# SERIAL_FMU3_REV_C.net
KiCad netlist of a schematic drawn in Altium Designer
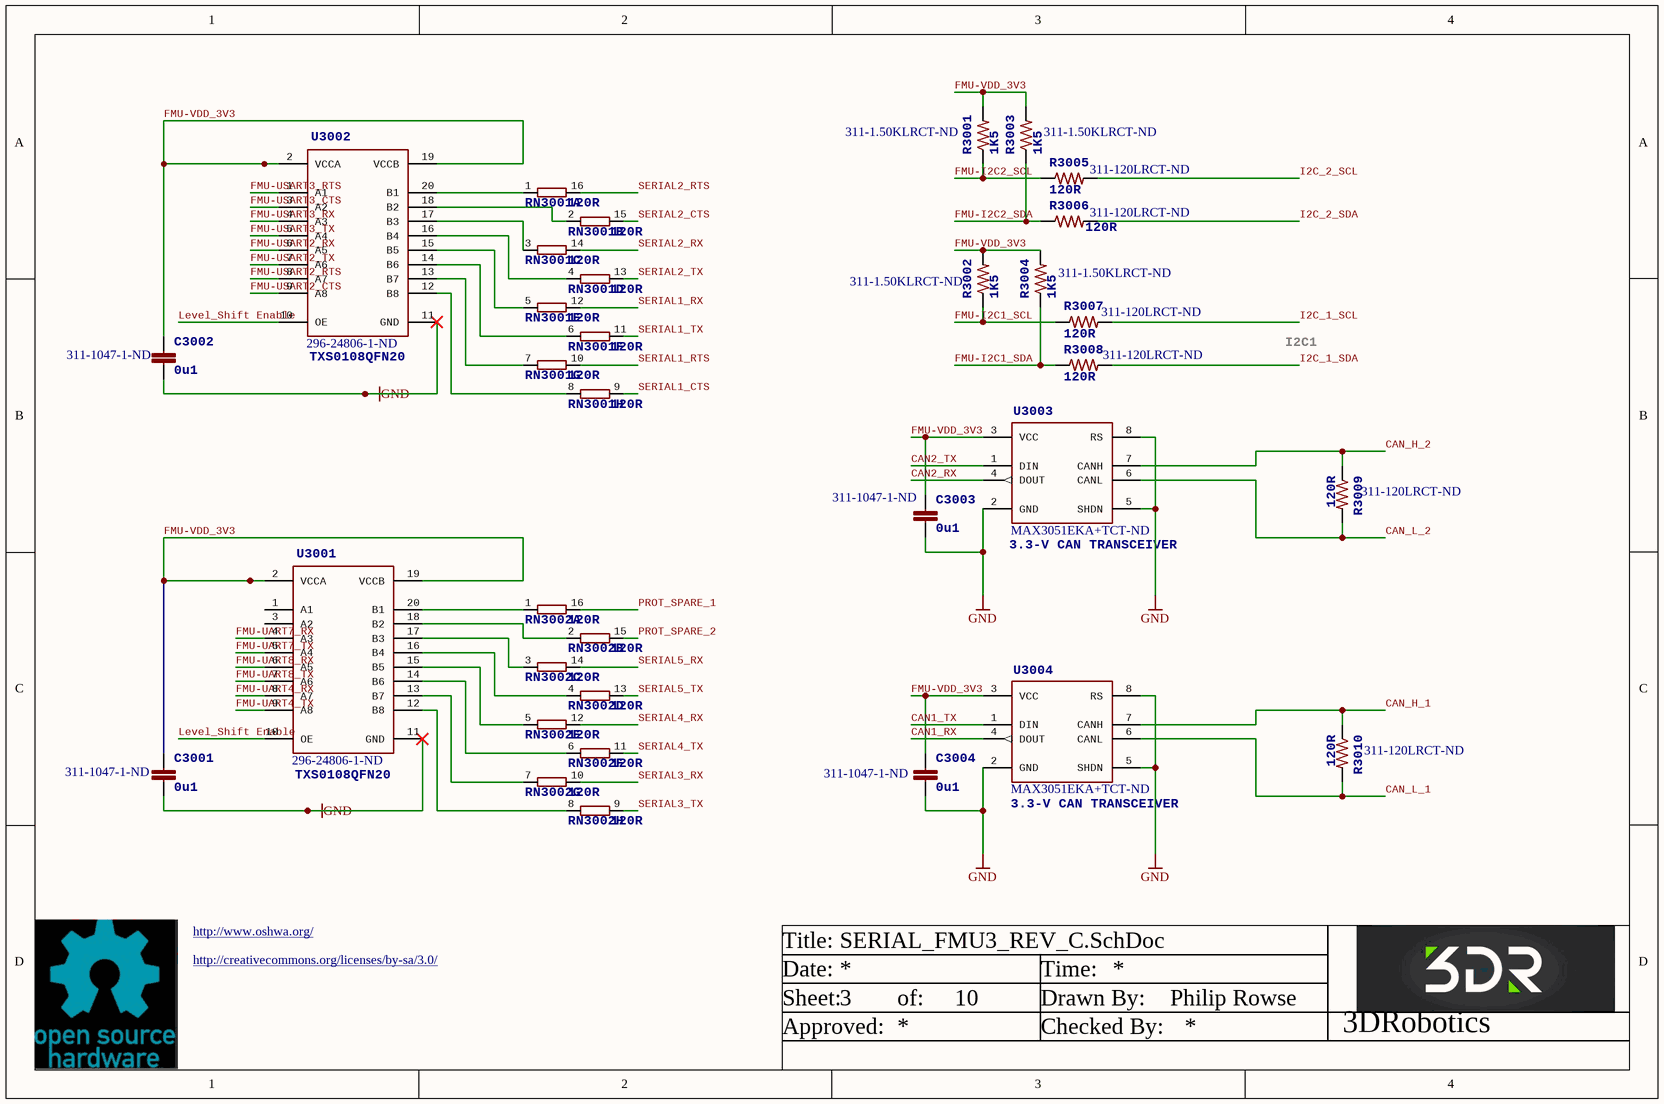
[diagram p0: SERIAL_FMU3_REV_C.SchDoc]

(export (version "E")
  (design (tool "Eeschema 10.0.6"))
  (components
    (comp (ref "C3001")
      (value "0u1")
      (footprint "0402-CAP")
      (description "CAP CER 0.1UF 16V Y5V 0402")
      (fields
        (field (name "PARTNO") "CC0402ZRY5V7BB104")
        (field (name "SUPPLIER PART NUMBER 1") "311-1047-1-ND")
        (field (name "3DR_PARTNO") "ECM0700")
      )
      (libsource (lib "pixhawk2") (part "CAP0402"))
    )
    (comp (ref "C3002")
      (value "0u1")
      (footprint "0402-CAP")
      (description "CAP CER 0.1UF 16V Y5V 0402")
      (fields
        (field (name "PARTNO") "CC0402ZRY5V7BB104")
        (field (name "SUPPLIER PART NUMBER 1") "311-1047-1-ND")
        (field (name "3DR_PARTNO") "ECM0700")
      )
      (libsource (lib "pixhawk2") (part "CAP0402"))
    )
    (comp (ref "C3003")
      (value "0u1")
      (footprint "0402-CAP")
      (description "CAP CER 0.1UF 16V Y5V 0402")
      (fields
        (field (name "PARTNO") "CC0402ZRY5V7BB104")
        (field (name "SUPPLIER PART NUMBER 1") "311-1047-1-ND")
        (field (name "3DR_PARTNO") "ECM0700")
      )
      (libsource (lib "pixhawk2") (part "CAP0402"))
    )
    (comp (ref "C3004")
      (value "0u1")
      (footprint "0402-CAP")
      (description "CAP CER 0.1UF 16V Y5V 0402")
      (fields
        (field (name "PARTNO") "CC0402ZRY5V7BB104")
        (field (name "SUPPLIER PART NUMBER 1") "311-1047-1-ND")
        (field (name "3DR_PARTNO") "ECM0700")
      )
      (libsource (lib "pixhawk2") (part "CAP0402"))
    )
    (comp (ref "R3001")
      (value "1K5")
      (footprint "0402-RES")
      (description "RES 1.5K OHM 1/16W 1% 0402 SMD")
      (fields
        (field (name "PARTNO") "RC0402FR-071K5L")
        (field (name "SUPPLIER PART NUMBER 1") "311-1.50KLRCT-ND")
        (field (name "3DR_PARTNO") "ECM0803")
      )
      (libsource (lib "pixhawk2") (part "RESISTOR0402-RES"))
    )
    (comp (ref "R3002")
      (value "1K5")
      (footprint "0402-RES")
      (description "RES 1.5K OHM 1/16W 1% 0402 SMD")
      (fields
        (field (name "PARTNO") "RC0402FR-071K5L")
        (field (name "SUPPLIER PART NUMBER 1") "311-1.50KLRCT-ND")
        (field (name "3DR_PARTNO") "ECM0803")
      )
      (libsource (lib "pixhawk2") (part "RESISTOR0402-RES"))
    )
    (comp (ref "R3003")
      (value "1K5")
      (footprint "0402-RES")
      (description "RES 1.5K OHM 1/16W 1% 0402 SMD")
      (fields
        (field (name "PARTNO") "RC0402FR-071K5L")
        (field (name "SUPPLIER PART NUMBER 1") "311-1.50KLRCT-ND")
        (field (name "3DR_PARTNO") "ECM0803")
      )
      (libsource (lib "pixhawk2") (part "RESISTOR0402-RES"))
    )
    (comp (ref "R3004")
      (value "1K5")
      (footprint "0402-RES")
      (description "RES 1.5K OHM 1/16W 1% 0402 SMD")
      (fields
        (field (name "PARTNO") "RC0402FR-071K5L")
        (field (name "SUPPLIER PART NUMBER 1") "311-1.50KLRCT-ND")
        (field (name "3DR_PARTNO") "ECM0803")
      )
      (libsource (lib "pixhawk2") (part "RESISTOR0402-RES"))
    )
    (comp (ref "R3005")
      (value "120R")
      (footprint "0402-RES")
      (description "RES 120 OHM 1/16W 1% 0402 SMD")
      (fields
        (field (name "PARTNO") "RC0402FR-07120RL")
        (field (name "SUPPLIER PART NUMBER 1") "311-120LRCT-ND")
        (field (name "3DR_PARTNO") "ECM0820")
      )
      (libsource (lib "pixhawk2") (part "RESISTOR0402-RES"))
    )
    (comp (ref "R3006")
      (value "120R")
      (footprint "0402-RES")
      (description "RES 120 OHM 1/16W 1% 0402 SMD")
      (fields
        (field (name "PARTNO") "RC0402FR-07120RL")
        (field (name "SUPPLIER PART NUMBER 1") "311-120LRCT-ND")
        (field (name "3DR_PARTNO") "ECM0820")
      )
      (libsource (lib "pixhawk2") (part "RESISTOR0402-RES"))
    )
    (comp (ref "R3007")
      (value "120R")
      (footprint "0402-RES")
      (description "RES 120 OHM 1/16W 1% 0402 SMD")
      (fields
        (field (name "PARTNO") "RC0402FR-07120RL")
        (field (name "SUPPLIER PART NUMBER 1") "311-120LRCT-ND")
        (field (name "3DR_PARTNO") "ECM0820")
      )
      (libsource (lib "pixhawk2") (part "RESISTOR0402-RES"))
    )
    (comp (ref "R3008")
      (value "120R")
      (footprint "0402-RES")
      (description "RES 120 OHM 1/16W 1% 0402 SMD")
      (fields
        (field (name "PARTNO") "RC0402FR-07120RL")
        (field (name "SUPPLIER PART NUMBER 1") "311-120LRCT-ND")
        (field (name "3DR_PARTNO") "ECM0820")
      )
      (libsource (lib "pixhawk2") (part "RESISTOR0402-RES"))
    )
    (comp (ref "R3009")
      (value "120R")
      (footprint "0402-RES")
      (description "RES 120 OHM 1/16W 1% 0402 SMD")
      (fields
        (field (name "PARTNO") "RC0402FR-07120RL")
        (field (name "SUPPLIER PART NUMBER 1") "311-120LRCT-ND")
        (field (name "3DR_PARTNO") "ECM0820")
      )
      (libsource (lib "pixhawk2") (part "RESISTOR0402-RES"))
    )
    (comp (ref "R3010")
      (value "120R")
      (footprint "0402-RES")
      (description "RES 120 OHM 1/16W 1% 0402 SMD")
      (fields
        (field (name "PARTNO") "RC0402FR-07120RL")
        (field (name "SUPPLIER PART NUMBER 1") "311-120LRCT-ND")
        (field (name "3DR_PARTNO") "ECM0820")
      )
      (libsource (lib "pixhawk2") (part "RESISTOR0402-RES"))
    )
    (comp (ref "RN3001")
      (value "120R")
      (footprint "EXB2HV")
      (description "RES ARRAY 120 OHM 8 RES 1506")
      (fields (field (name "PARTNO") "EXB-2HV121JV") (field (name "3DR_PARTNO") "EMC"))
      (libsource (lib "pixhawk2") (part "8R-NEXB2HV-120R"))
    )
    (comp (ref "RN3002")
      (value "120R")
      (footprint "EXB2HV")
      (description "RES ARRAY 120 OHM 8 RES 1506")
      (fields (field (name "PARTNO") "EXB-2HV121JV") (field (name "3DR_PARTNO") "EMC"))
      (libsource (lib "pixhawk2") (part "8R-NEXB2HV-120R"))
    )
    (comp (ref "U3001")
      (value "TXS0108QFN20")
      (footprint "QFN20-RGY")
      (description "IC XLATR VOLT-LVL 8B BDIR 20QFN")
      (fields
        (field (name "SUPPLIER PART NUMBER 1") "296-24806-1-ND")
        (field (name "3DR_PARTNO") "ECM0845")
        (field (name "PARTNO") "TXS0108ERGYR")
      )
      (libsource (lib "pixhawk2") (part "TXS0108QFN20"))
    )
    (comp (ref "U3002")
      (value "TXS0108QFN20")
      (footprint "QFN20-RGY")
      (description "IC XLATR VOLT-LVL 8B BDIR 20QFN")
      (fields
        (field (name "SUPPLIER PART NUMBER 1") "296-24806-1-ND")
        (field (name "3DR_PARTNO") "ECM0845")
        (field (name "PARTNO") "TXS0108ERGYR")
      )
      (libsource (lib "pixhawk2") (part "TXS0108QFN20"))
    )
    (comp (ref "U3003")
      (value "3.3-V CAN TRANSCEIVER")
      (footprint "SOT23-8")
      (description "IC TXRX CAN 1MBPS SOT23-8")
      (fields
        (field (name "SUPPLIER PART NUMBER 1") "MAX3051EKA+TCT-ND")
        (field (name "3DR_PARTNO") "ECM0831")
        (field (name "PARTNO") "MAX3051EKA+T")
      )
      (libsource (lib "pixhawk2") (part "MAX3051MAX3051EKA"))
    )
    (comp (ref "U3004")
      (value "3.3-V CAN TRANSCEIVER")
      (footprint "SOT23-8")
      (description "IC TXRX CAN 1MBPS SOT23-8")
      (fields
        (field (name "SUPPLIER PART NUMBER 1") "MAX3051EKA+TCT-ND")
        (field (name "3DR_PARTNO") "ECM0831")
        (field (name "PARTNO") "MAX3051EKA+T")
      )
      (libsource (lib "pixhawk2") (part "MAX3051MAX3051EKA"))
    )
  )
  (nets
    (net (code "1") (name "/CAN1_RX") (class "Default")
      (node (ref "U3004") (pin "4") (pinfunction "DOUT_4") (pintype "output"))
    )
    (net (code "2") (name "/CAN1_TX") (class "Default")
      (node (ref "U3004") (pin "1") (pinfunction "DIN_1") (pintype "passive"))
    )
    (net (code "3") (name "/CAN2_RX") (class "Default")
      (node (ref "U3003") (pin "4") (pinfunction "DOUT_4") (pintype "output"))
    )
    (net (code "4") (name "/CAN2_TX") (class "Default")
      (node (ref "U3003") (pin "1") (pinfunction "DIN_1") (pintype "passive"))
    )
    (net (code "5") (name "/CAN_H_1") (class "Default")
      (node (ref "R3010") (pin "P$1") (pinfunction "1_P$1") (pintype "passive"))
      (node (ref "U3004") (pin "7") (pinfunction "CANH_7") (pintype "passive"))
    )
    (net (code "6") (name "/CAN_H_2") (class "Default")
      (node (ref "R3009") (pin "P$1") (pinfunction "1_P$1") (pintype "passive"))
      (node (ref "U3003") (pin "7") (pinfunction "CANH_7") (pintype "passive"))
    )
    (net (code "7") (name "/CAN_L_1") (class "Default")
      (node (ref "R3010") (pin "P$2") (pinfunction "2_P$2") (pintype "passive"))
      (node (ref "U3004") (pin "6") (pinfunction "CANL_6") (pintype "passive"))
    )
    (net (code "8") (name "/CAN_L_2") (class "Default")
      (node (ref "R3009") (pin "P$2") (pinfunction "2_P$2") (pintype "passive"))
      (node (ref "U3003") (pin "6") (pinfunction "CANL_6") (pintype "passive"))
    )
    (net (code "9") (name "/FMU-I2C1_SCL") (class "Default")
      (node (ref "R3002") (pin "P$1") (pinfunction "1_P$1") (pintype "passive"))
      (node (ref "R3007") (pin "P$1") (pinfunction "1_P$1") (pintype "passive"))
    )
    (net (code "10") (name "/FMU-I2C1_SDA") (class "Default")
      (node (ref "R3004") (pin "P$1") (pinfunction "1_P$1") (pintype "passive"))
      (node (ref "R3008") (pin "P$1") (pinfunction "1_P$1") (pintype "passive"))
    )
    (net (code "11") (name "/FMU-I2C2_SCL") (class "Default")
      (node (ref "R3001") (pin "P$1") (pinfunction "1_P$1") (pintype "passive"))
      (node (ref "R3005") (pin "P$1") (pinfunction "1_P$1") (pintype "passive"))
    )
    (net (code "12") (name "/FMU-I2C2_SDA") (class "Default")
      (node (ref "R3003") (pin "P$1") (pinfunction "1_P$1") (pintype "passive"))
      (node (ref "R3006") (pin "P$1") (pinfunction "1_P$1") (pintype "passive"))
    )
    (net (code "13") (name "/FMU-UART4_RX") (class "Default")
      (node (ref "U3001") (pin "8") (pinfunction "A7_8") (pintype "passive"))
    )
    (net (code "14") (name "/FMU-UART4_TX") (class "Default")
      (node (ref "U3001") (pin "9") (pinfunction "A8_9") (pintype "passive"))
    )
    (net (code "15") (name "/FMU-UART7_RX") (class "Default")
      (node (ref "U3001") (pin "4") (pinfunction "A3_4") (pintype "passive"))
    )
    (net (code "16") (name "/FMU-UART7_TX") (class "Default")
      (node (ref "U3001") (pin "5") (pinfunction "A4_5") (pintype "passive"))
    )
    (net (code "17") (name "/FMU-UART8_RX") (class "Default")
      (node (ref "U3001") (pin "6") (pinfunction "A5_6") (pintype "passive"))
    )
    (net (code "18") (name "/FMU-UART8_TX") (class "Default")
      (node (ref "U3001") (pin "7") (pinfunction "A6_7") (pintype "passive"))
    )
    (net (code "19") (name "/FMU-USART2_CTS") (class "Default")
      (node (ref "U3002") (pin "9") (pinfunction "A8_9") (pintype "passive"))
    )
    (net (code "20") (name "/FMU-USART2_RTS") (class "Default")
      (node (ref "U3002") (pin "8") (pinfunction "A7_8") (pintype "passive"))
    )
    (net (code "21") (name "/FMU-USART2_RX") (class "Default")
      (node (ref "U3002") (pin "6") (pinfunction "A5_6") (pintype "passive"))
    )
    (net (code "22") (name "/FMU-USART2_TX") (class "Default")
      (node (ref "U3002") (pin "7") (pinfunction "A6_7") (pintype "passive"))
    )
    (net (code "23") (name "/FMU-USART3_CTS") (class "Default")
      (node (ref "U3002") (pin "3") (pinfunction "A2_3") (pintype "passive"))
    )
    (net (code "24") (name "/FMU-USART3_RTS") (class "Default")
      (node (ref "U3002") (pin "1") (pinfunction "A1_1") (pintype "passive"))
    )
    (net (code "25") (name "/FMU-USART3_RX") (class "Default")
      (node (ref "U3002") (pin "4") (pinfunction "A3_4") (pintype "passive"))
    )
    (net (code "26") (name "/FMU-USART3_TX") (class "Default")
      (node (ref "U3002") (pin "5") (pinfunction "A4_5") (pintype "passive"))
    )
    (net (code "27") (name "/FMU-VDD_3V3") (class "Default")
      (node (ref "C3001") (pin "P$1") (pinfunction "1_P$1") (pintype "passive"))
      (node (ref "C3002") (pin "P$1") (pinfunction "1_P$1") (pintype "passive"))
      (node (ref "C3003") (pin "P$1") (pinfunction "1_P$1") (pintype "passive"))
      (node (ref "C3004") (pin "P$1") (pinfunction "1_P$1") (pintype "passive"))
      (node (ref "R3001") (pin "P$2") (pinfunction "2_P$2") (pintype "passive"))
      (node (ref "R3002") (pin "P$2") (pinfunction "2_P$2") (pintype "passive"))
      (node (ref "R3003") (pin "P$2") (pinfunction "2_P$2") (pintype "passive"))
      (node (ref "R3004") (pin "P$2") (pinfunction "2_P$2") (pintype "passive"))
      (node (ref "U3001") (pin "19") (pinfunction "VCCB_19") (pintype "passive"))
      (node (ref "U3001") (pin "2") (pinfunction "VCCA_2") (pintype "passive"))
      (node (ref "U3002") (pin "19") (pinfunction "VCCB_19") (pintype "passive"))
      (node (ref "U3002") (pin "2") (pinfunction "VCCA_2") (pintype "passive"))
      (node (ref "U3003") (pin "3") (pinfunction "VCC_3") (pintype "passive"))
      (node (ref "U3004") (pin "3") (pinfunction "VCC_3") (pintype "passive"))
    )
    (net (code "28") (name "/I2C_1_SCL") (class "Default")
      (node (ref "R3007") (pin "P$2") (pinfunction "2_P$2") (pintype "passive"))
    )
    (net (code "29") (name "/I2C_1_SDA") (class "Default")
      (node (ref "R3008") (pin "P$2") (pinfunction "2_P$2") (pintype "passive"))
    )
    (net (code "30") (name "/I2C_2_SCL") (class "Default")
      (node (ref "R3005") (pin "P$2") (pinfunction "2_P$2") (pintype "passive"))
    )
    (net (code "31") (name "/I2C_2_SDA") (class "Default")
      (node (ref "R3006") (pin "P$2") (pinfunction "2_P$2") (pintype "passive"))
    )
    (net (code "32") (name "/Level_Shift Enable") (class "Default")
      (node (ref "U3001") (pin "10") (pinfunction "OE_10") (pintype "passive"))
      (node (ref "U3002") (pin "10") (pinfunction "OE_10") (pintype "passive"))
    )
    (net (code "33") (name "/PROT_SPARE_1") (class "Default")
      (node (ref "RN3002") (pin "16") (pinfunction "2_16") (pintype "passive"))
    )
    (net (code "34") (name "/PROT_SPARE_2") (class "Default")
      (node (ref "RN3002") (pin "15") (pinfunction "2_15") (pintype "passive"))
    )
    (net (code "35") (name "/SERIAL1_CTS") (class "Default")
      (node (ref "RN3001") (pin "9") (pinfunction "2_9") (pintype "passive"))
    )
    (net (code "36") (name "/SERIAL1_RTS") (class "Default")
      (node (ref "RN3001") (pin "10") (pinfunction "2_10") (pintype "passive"))
    )
    (net (code "37") (name "/SERIAL1_RX") (class "Default")
      (node (ref "RN3001") (pin "12") (pinfunction "2_12") (pintype "passive"))
    )
    (net (code "38") (name "/SERIAL1_TX") (class "Default")
      (node (ref "RN3001") (pin "11") (pinfunction "2_11") (pintype "passive"))
    )
    (net (code "39") (name "/SERIAL2_CTS") (class "Default")
      (node (ref "RN3001") (pin "15") (pinfunction "2_15") (pintype "passive"))
    )
    (net (code "40") (name "/SERIAL2_RTS") (class "Default")
      (node (ref "RN3001") (pin "16") (pinfunction "2_16") (pintype "passive"))
    )
    (net (code "41") (name "/SERIAL2_RX") (class "Default")
      (node (ref "RN3001") (pin "14") (pinfunction "2_14") (pintype "passive"))
    )
    (net (code "42") (name "/SERIAL2_TX") (class "Default")
      (node (ref "RN3001") (pin "13") (pinfunction "2_13") (pintype "passive"))
    )
    (net (code "43") (name "/SERIAL3_RX") (class "Default")
      (node (ref "RN3002") (pin "10") (pinfunction "2_10") (pintype "passive"))
    )
    (net (code "44") (name "/SERIAL3_TX") (class "Default")
      (node (ref "RN3002") (pin "9") (pinfunction "2_9") (pintype "passive"))
    )
    (net (code "45") (name "/SERIAL4_RX") (class "Default")
      (node (ref "RN3002") (pin "12") (pinfunction "2_12") (pintype "passive"))
    )
    (net (code "46") (name "/SERIAL4_TX") (class "Default")
      (node (ref "RN3002") (pin "11") (pinfunction "2_11") (pintype "passive"))
    )
    (net (code "47") (name "/SERIAL5_RX") (class "Default")
      (node (ref "RN3002") (pin "14") (pinfunction "2_14") (pintype "passive"))
    )
    (net (code "48") (name "/SERIAL5_TX") (class "Default")
      (node (ref "RN3002") (pin "13") (pinfunction "2_13") (pintype "passive"))
    )
    (net (code "49") (name "GND") (class "Default")
      (node (ref "C3001") (pin "P$2") (pinfunction "2_P$2") (pintype "passive"))
      (node (ref "C3002") (pin "P$2") (pinfunction "2_P$2") (pintype "passive"))
      (node (ref "C3003") (pin "P$2") (pinfunction "2_P$2") (pintype "passive"))
      (node (ref "C3004") (pin "P$2") (pinfunction "2_P$2") (pintype "passive"))
      (node (ref "U3001") (pin "11") (pinfunction "GND_11") (pintype "open_emitter"))
      (node (ref "U3002") (pin "11") (pinfunction "GND_11") (pintype "open_emitter"))
      (node (ref "U3003") (pin "2") (pinfunction "GND_2") (pintype "open_emitter"))
      (node (ref "U3003") (pin "5") (pinfunction "SHDN_5") (pintype "passive"))
      (node (ref "U3003") (pin "8") (pinfunction "RS_8") (pintype "passive"))
      (node (ref "U3004") (pin "2") (pinfunction "GND_2") (pintype "open_emitter"))
      (node (ref "U3004") (pin "5") (pinfunction "SHDN_5") (pintype "passive"))
      (node (ref "U3004") (pin "8") (pinfunction "RS_8") (pintype "passive"))
    )
    (net (code "50") (name "Net-(RN3001B-1)") (class "Default")
      (node (ref "RN3001") (pin "2") (pinfunction "1_2") (pintype "passive"))
      (node (ref "U3002") (pin "18") (pinfunction "B2_18") (pintype "passive"))
    )
    (net (code "51") (name "Net-(RN3001C-1)") (class "Default")
      (node (ref "RN3001") (pin "3") (pinfunction "1_3") (pintype "passive"))
      (node (ref "U3002") (pin "17") (pinfunction "B3_17") (pintype "passive"))
    )
    (net (code "52") (name "Net-(RN3001D-1)") (class "Default")
      (node (ref "RN3001") (pin "4") (pinfunction "1_4") (pintype "passive"))
      (node (ref "U3002") (pin "16") (pinfunction "B4_16") (pintype "passive"))
    )
    (net (code "53") (name "Net-(RN3001E-1)") (class "Default")
      (node (ref "RN3001") (pin "5") (pinfunction "1_5") (pintype "passive"))
      (node (ref "U3002") (pin "15") (pinfunction "B5_15") (pintype "passive"))
    )
    (net (code "54") (name "Net-(RN3001F-1)") (class "Default")
      (node (ref "RN3001") (pin "6") (pinfunction "1_6") (pintype "passive"))
      (node (ref "U3002") (pin "14") (pinfunction "B6_14") (pintype "passive"))
    )
    (net (code "55") (name "Net-(RN3001G-1)") (class "Default")
      (node (ref "RN3001") (pin "7") (pinfunction "1_7") (pintype "passive"))
      (node (ref "U3002") (pin "13") (pinfunction "B7_13") (pintype "passive"))
    )
    (net (code "56") (name "Net-(RN3001H-1)") (class "Default")
      (node (ref "RN3001") (pin "8") (pinfunction "1_8") (pintype "passive"))
      (node (ref "U3002") (pin "12") (pinfunction "B8_12") (pintype "passive"))
    )
    (net (code "57") (name "Net-(RN3002B-1)") (class "Default")
      (node (ref "RN3002") (pin "2") (pinfunction "1_2") (pintype "passive"))
      (node (ref "U3001") (pin "18") (pinfunction "B2_18") (pintype "passive"))
    )
    (net (code "58") (name "Net-(RN3002C-1)") (class "Default")
      (node (ref "RN3002") (pin "3") (pinfunction "1_3") (pintype "passive"))
      (node (ref "U3001") (pin "17") (pinfunction "B3_17") (pintype "passive"))
    )
    (net (code "59") (name "Net-(RN3002D-1)") (class "Default")
      (node (ref "RN3002") (pin "4") (pinfunction "1_4") (pintype "passive"))
      (node (ref "U3001") (pin "16") (pinfunction "B4_16") (pintype "passive"))
    )
    (net (code "60") (name "Net-(RN3002E-1)") (class "Default")
      (node (ref "RN3002") (pin "5") (pinfunction "1_5") (pintype "passive"))
      (node (ref "U3001") (pin "15") (pinfunction "B5_15") (pintype "passive"))
    )
    (net (code "61") (name "Net-(RN3002F-1)") (class "Default")
      (node (ref "RN3002") (pin "6") (pinfunction "1_6") (pintype "passive"))
      (node (ref "U3001") (pin "14") (pinfunction "B6_14") (pintype "passive"))
    )
    (net (code "62") (name "Net-(RN3002G-1)") (class "Default")
      (node (ref "RN3002") (pin "7") (pinfunction "1_7") (pintype "passive"))
      (node (ref "U3001") (pin "13") (pinfunction "B7_13") (pintype "passive"))
    )
    (net (code "63") (name "Net-(RN3002H-1)") (class "Default")
      (node (ref "RN3002") (pin "8") (pinfunction "1_8") (pintype "passive"))
      (node (ref "U3001") (pin "12") (pinfunction "B8_12") (pintype "passive"))
    )
    (net (code "64") (name "Net-(U3001-B1)") (class "Default")
      (node (ref "RN3002") (pin "1") (pinfunction "1_1") (pintype "passive"))
      (node (ref "U3001") (pin "20") (pinfunction "B1_20") (pintype "passive"))
    )
    (net (code "65") (name "Net-(U3002-B1)") (class "Default")
      (node (ref "RN3001") (pin "1") (pinfunction "1_1") (pintype "passive"))
      (node (ref "U3002") (pin "20") (pinfunction "B1_20") (pintype "passive"))
    )
    (net (code "66") (name "unconnected-(U3001-A1-Pad1)") (class "Default")
      (node (ref "U3001") (pin "1") (pinfunction "A1_1") (pintype "passive"))
    )
    (net (code "67") (name "unconnected-(U3001-A2-Pad3)") (class "Default")
      (node (ref "U3001") (pin "3") (pinfunction "A2_3") (pintype "passive"))
    )
  )
)
